# CommsTestBoard.net
KiCad netlist of a schematic drawn in EAGLE
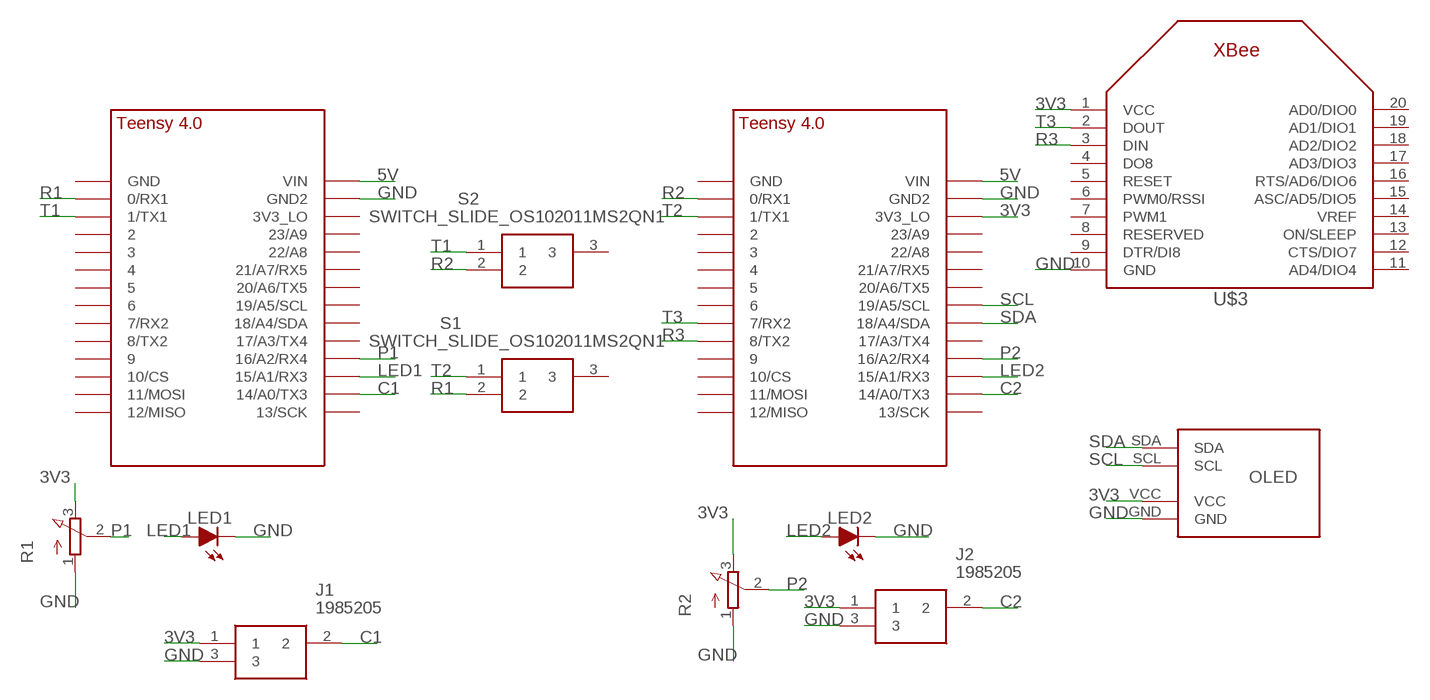
[diagram p0: schematic, sheet 1]

(export (version "E")
  (design (tool "Eeschema 10.0.6"))
  (components
    (comp (ref "J1")
      (value "1985205")
      (footprint "eagle-import:1985205")
      (fields (field (name "MOUSER_PART_NUMBER") "651-1985205"))
      (libsource (lib "eagle-import") (part "1985205"))
    )
    (comp (ref "J2")
      (value "1985205")
      (footprint "eagle-import:1985205")
      (fields (field (name "MOUSER_PART_NUMBER") "651-1985205"))
      (libsource (lib "eagle-import") (part "1985205"))
    )
    (comp (ref "LED1")
      (value "LED-5MM")
      (footprint "eagle-import:LED-5MM")
      (libsource (lib "eagle-import") (part "LED-5MM"))
    )
    (comp (ref "LED2")
      (value "LED-5MM")
      (footprint "eagle-import:LED-5MM")
      (libsource (lib "eagle-import") (part "LED-5MM"))
    )
    (comp (ref "R1")
      (value "POTENTIOMETER")
      (footprint "eagle-import:3RP_1610N")
      (libsource (lib "eagle-import") (part "POTENTIOMETER"))
    )
    (comp (ref "R2")
      (value "POTENTIOMETER")
      (footprint "eagle-import:3RP_1610N")
      (libsource (lib "eagle-import") (part "POTENTIOMETER"))
    )
    (comp (ref "S1")
      (value "SWITCH_SLIDE_OS102011MS2QN1")
      (footprint "eagle-import:OS102011MA1QN1")
      (fields
        (field (name "ARROW_PART_NUMBER") "OS102011MS2QN1")
        (field (name "MOUSER_PART_NUMBER") "611-OS102011MS2QN1")
      )
      (libsource (lib "eagle-import") (part "SWITCH_SLIDE_OS102011MS2QN1"))
    )
    (comp (ref "S2")
      (value "SWITCH_SLIDE_OS102011MS2QN1")
      (footprint "eagle-import:OS102011MA1QN1")
      (fields
        (field (name "ARROW_PART_NUMBER") "OS102011MS2QN1")
        (field (name "MOUSER_PART_NUMBER") "611-OS102011MS2QN1")
      )
      (libsource (lib "eagle-import") (part "SWITCH_SLIDE_OS102011MS2QN1"))
    )
    (comp (ref "U$1")
      (value "TEENSY_4.0_SIMPLE")
      (footprint "eagle-import:TEENSY_4.0_SIMPLE")
      (libsource (lib "eagle-import") (part "TEENSY_4.0_SIMPLE"))
    )
    (comp (ref "U$2")
      (value "TEENSY_4.0_SIMPLE")
      (footprint "eagle-import:TEENSY_4.0_SIMPLE")
      (libsource (lib "eagle-import") (part "TEENSY_4.0_SIMPLE"))
    )
    (comp (ref "U$3")
      (value "XBEE")
      (footprint "eagle-import:XBEE")
      (libsource (lib "eagle-import") (part "XBEE"))
    )
    (comp (ref "U$4")
      (value "OLED_SSD1306")
      (footprint "eagle-import:OLED_SSD1306")
      (libsource (lib "eagle-import") (part "OLED_SSD1306"))
    )
  )
  (nets
    (net (code "1") (name "/3V3") (class "Default")
      (node (ref "J1") (pin "1") (pinfunction "1_1") (pintype "bidirectional"))
      (node (ref "J2") (pin "1") (pinfunction "1_1") (pintype "bidirectional"))
      (node (ref "R1") (pin "3") (pinfunction "E_3") (pintype "passive"))
      (node (ref "R2") (pin "3") (pinfunction "E_3") (pintype "passive"))
      (node (ref "U$2") (pin "3V3_LO") (pinfunction "3V3_LO_3V3_LO") (pintype "bidirectional"))
      (node (ref "U$3") (pin "1") (pinfunction "VCC_1") (pintype "power_in"))
      (node (ref "U$4") (pin "VCC") (pinfunction "VCC_VCC") (pintype "bidirectional"))
    )
    (net (code "2") (name "/5V") (class "Default")
      (node (ref "U$1") (pin "VIN") (pinfunction "VIN_VIN") (pintype "bidirectional"))
      (node (ref "U$2") (pin "VIN") (pinfunction "VIN_VIN") (pintype "bidirectional"))
    )
    (net (code "3") (name "/C1") (class "Default")
      (node (ref "J1") (pin "2") (pinfunction "2_2") (pintype "bidirectional"))
      (node (ref "U$1") (pin "14/A0") (pinfunction "14/A0/TX3_14/A0") (pintype "bidirectional"))
    )
    (net (code "4") (name "/C2") (class "Default")
      (node (ref "J2") (pin "2") (pinfunction "2_2") (pintype "bidirectional"))
      (node (ref "U$2") (pin "14/A0") (pinfunction "14/A0/TX3_14/A0") (pintype "bidirectional"))
    )
    (net (code "5") (name "/GND") (class "Default")
      (node (ref "J1") (pin "3") (pinfunction "3_3") (pintype "bidirectional"))
      (node (ref "J2") (pin "3") (pinfunction "3_3") (pintype "bidirectional"))
      (node (ref "LED1") (pin "K") (pinfunction "C_K") (pintype "passive"))
      (node (ref "LED2") (pin "K") (pinfunction "C_K") (pintype "passive"))
      (node (ref "R1") (pin "1") (pinfunction "A_1") (pintype "passive"))
      (node (ref "R2") (pin "1") (pinfunction "A_1") (pintype "passive"))
      (node (ref "U$1") (pin "GND2") (pinfunction "GND2_GND2") (pintype "bidirectional"))
      (node (ref "U$2") (pin "GND2") (pinfunction "GND2_GND2") (pintype "bidirectional"))
      (node (ref "U$3") (pin "10") (pinfunction "GND_10") (pintype "power_in"))
      (node (ref "U$4") (pin "GND") (pinfunction "GND_GND") (pintype "bidirectional"))
    )
    (net (code "6") (name "/LED1") (class "Default")
      (node (ref "LED1") (pin "A") (pinfunction "A_A") (pintype "passive"))
      (node (ref "U$1") (pin "15/A1") (pinfunction "15/A1/RX3_15/A1") (pintype "bidirectional"))
    )
    (net (code "7") (name "/LED2") (class "Default")
      (node (ref "LED2") (pin "A") (pinfunction "A_A") (pintype "passive"))
      (node (ref "U$2") (pin "15/A1") (pinfunction "15/A1/RX3_15/A1") (pintype "bidirectional"))
    )
    (net (code "8") (name "/P1") (class "Default")
      (node (ref "R1") (pin "2") (pinfunction "S_2") (pintype "passive"))
      (node (ref "U$1") (pin "16/A2") (pinfunction "16/A2/RX4_16/A2") (pintype "bidirectional"))
    )
    (net (code "9") (name "/P2") (class "Default")
      (node (ref "R2") (pin "2") (pinfunction "S_2") (pintype "passive"))
      (node (ref "U$2") (pin "16/A2") (pinfunction "16/A2/RX4_16/A2") (pintype "bidirectional"))
    )
    (net (code "10") (name "/R1") (class "Default")
      (node (ref "S1") (pin "2") (pinfunction "2_2") (pintype "bidirectional"))
      (node (ref "U$1") (pin "0/RX") (pinfunction "0/RX1_0/RX") (pintype "bidirectional"))
    )
    (net (code "11") (name "/R2") (class "Default")
      (node (ref "S2") (pin "2") (pinfunction "2_2") (pintype "bidirectional"))
      (node (ref "U$2") (pin "0/RX") (pinfunction "0/RX1_0/RX") (pintype "bidirectional"))
    )
    (net (code "12") (name "/R3") (class "Default")
      (node (ref "U$2") (pin "8") (pinfunction "8/TX2_8") (pintype "bidirectional"))
      (node (ref "U$3") (pin "3") (pinfunction "DIN_3") (pintype "input"))
    )
    (net (code "13") (name "/SCL") (class "Default")
      (node (ref "U$2") (pin "19/A5/SCL") (pinfunction "19/A5/SCL_19/A5/SCL") (pintype "bidirectional"))
      (node (ref "U$4") (pin "SCL") (pinfunction "SCL_SCL") (pintype "bidirectional"))
    )
    (net (code "14") (name "/SDA") (class "Default")
      (node (ref "U$2") (pin "18/A4/SDA") (pinfunction "18/A4/SDA_18/A4/SDA") (pintype "bidirectional"))
      (node (ref "U$4") (pin "SDA") (pinfunction "SDA_SDA") (pintype "bidirectional"))
    )
    (net (code "15") (name "/T1") (class "Default")
      (node (ref "S2") (pin "1") (pinfunction "1_1") (pintype "bidirectional"))
      (node (ref "U$1") (pin "1/TX") (pinfunction "1/TX1_1/TX") (pintype "bidirectional"))
    )
    (net (code "16") (name "/T2") (class "Default")
      (node (ref "S1") (pin "1") (pinfunction "1_1") (pintype "bidirectional"))
      (node (ref "U$2") (pin "1/TX") (pinfunction "1/TX1_1/TX") (pintype "bidirectional"))
    )
    (net (code "17") (name "/T3") (class "Default")
      (node (ref "U$2") (pin "7") (pinfunction "7/RX2_7") (pintype "bidirectional"))
      (node (ref "U$3") (pin "2") (pinfunction "DOUT_2") (pintype "output"))
    )
    (net (code "18") (name "unconnected-(S1-Pad3)") (class "Default")
      (node (ref "S1") (pin "3") (pinfunction "3_3") (pintype "bidirectional"))
    )
    (net (code "19") (name "unconnected-(S2-Pad3)") (class "Default")
      (node (ref "S2") (pin "3") (pinfunction "3_3") (pintype "bidirectional"))
    )
    (net (code "20") (name "unconnected-(U$1-3-Pad3{slash}CANTX)") (class "Default")
      (node (ref "U$1") (pin "3/CANTX") (pinfunction "3_3/CANTX") (pintype "bidirectional"))
    )
    (net (code "21") (name "unconnected-(U$1-4-Pad4{slash}CANRX)") (class "Default")
      (node (ref "U$1") (pin "4/CANRX") (pinfunction "4_4/CANRX") (pintype "bidirectional"))
    )
    (net (code "22") (name "unconnected-(U$1-7{slash}RX2-Pad7)") (class "Default")
      (node (ref "U$1") (pin "7") (pinfunction "7/RX2_7") (pintype "bidirectional"))
    )
    (net (code "23") (name "unconnected-(U$1-8{slash}TX2-Pad8)") (class "Default")
      (node (ref "U$1") (pin "8") (pinfunction "8/TX2_8") (pintype "bidirectional"))
    )
    (net (code "24") (name "unconnected-(U$1-9-Pad9{slash}CS)") (class "Default")
      (node (ref "U$1") (pin "9/CS") (pinfunction "9_9/CS") (pintype "bidirectional"))
    )
    (net (code "25") (name "unconnected-(U$1-17{slash}A3{slash}TX4-Pad17{slash}A3)") (class "Default")
      (node (ref "U$1") (pin "17/A3") (pinfunction "17/A3/TX4_17/A3") (pintype "bidirectional"))
    )
    (net (code "26") (name "unconnected-(U$1-20{slash}A6{slash}TX5-Pad20{slash}A6)") (class "Default")
      (node (ref "U$1") (pin "20/A6") (pinfunction "20/A6/TX5_20/A6") (pintype "bidirectional"))
    )
    (net (code "27") (name "unconnected-(U$1-21{slash}A7{slash}RX5-Pad21{slash}A7)") (class "Default")
      (node (ref "U$1") (pin "21/A7") (pinfunction "21/A7/RX5_21/A7") (pintype "bidirectional"))
    )
    (net (code "28") (name "unconnected-(U$1-Pad2)") (class "Default")
      (node (ref "U$1") (pin "2") (pinfunction "2_2") (pintype "bidirectional"))
    )
    (net (code "29") (name "unconnected-(U$1-Pad3V3_LO)") (class "Default")
      (node (ref "U$1") (pin "3V3_LO") (pinfunction "3V3_LO_3V3_LO") (pintype "bidirectional"))
    )
    (net (code "30") (name "unconnected-(U$1-Pad5)") (class "Default")
      (node (ref "U$1") (pin "5") (pinfunction "5_5") (pintype "bidirectional"))
    )
    (net (code "31") (name "unconnected-(U$1-Pad6)") (class "Default")
      (node (ref "U$1") (pin "6") (pinfunction "6_6") (pintype "bidirectional"))
    )
    (net (code "32") (name "unconnected-(U$1-Pad10{slash}CS)") (class "Default")
      (node (ref "U$1") (pin "10/CS") (pinfunction "10/CS_10/CS") (pintype "bidirectional"))
    )
    (net (code "33") (name "unconnected-(U$1-Pad11{slash}MOSI)") (class "Default")
      (node (ref "U$1") (pin "11/MOSI") (pinfunction "11/MOSI_11/MOSI") (pintype "bidirectional"))
    )
    (net (code "34") (name "unconnected-(U$1-Pad12{slash}MISO)") (class "Default")
      (node (ref "U$1") (pin "12/MISO") (pinfunction "12/MISO_12/MISO") (pintype "bidirectional"))
    )
    (net (code "35") (name "unconnected-(U$1-Pad13{slash}SCK)") (class "Default")
      (node (ref "U$1") (pin "13/SCK") (pinfunction "13/SCK_13/SCK") (pintype "bidirectional"))
    )
    (net (code "36") (name "unconnected-(U$1-Pad18{slash}A4{slash}SDA)") (class "Default")
      (node (ref "U$1") (pin "18/A4/SDA") (pinfunction "18/A4/SDA_18/A4/SDA") (pintype "bidirectional"))
    )
    (net (code "37") (name "unconnected-(U$1-Pad19{slash}A5{slash}SCL)") (class "Default")
      (node (ref "U$1") (pin "19/A5/SCL") (pinfunction "19/A5/SCL_19/A5/SCL") (pintype "bidirectional"))
    )
    (net (code "38") (name "unconnected-(U$1-Pad22{slash}A8)") (class "Default")
      (node (ref "U$1") (pin "22/A8") (pinfunction "22/A8_22/A8") (pintype "bidirectional"))
    )
    (net (code "39") (name "unconnected-(U$1-Pad23{slash}A9)") (class "Default")
      (node (ref "U$1") (pin "23/A9") (pinfunction "23/A9_23/A9") (pintype "bidirectional"))
    )
    (net (code "40") (name "unconnected-(U$1-PadGND)") (class "Default")
      (node (ref "U$1") (pin "GND") (pinfunction "GND_GND") (pintype "bidirectional"))
    )
    (net (code "41") (name "unconnected-(U$2-3-Pad3{slash}CANTX)") (class "Default")
      (node (ref "U$2") (pin "3/CANTX") (pinfunction "3_3/CANTX") (pintype "bidirectional"))
    )
    (net (code "42") (name "unconnected-(U$2-4-Pad4{slash}CANRX)") (class "Default")
      (node (ref "U$2") (pin "4/CANRX") (pinfunction "4_4/CANRX") (pintype "bidirectional"))
    )
    (net (code "43") (name "unconnected-(U$2-9-Pad9{slash}CS)") (class "Default")
      (node (ref "U$2") (pin "9/CS") (pinfunction "9_9/CS") (pintype "bidirectional"))
    )
    (net (code "44") (name "unconnected-(U$2-17{slash}A3{slash}TX4-Pad17{slash}A3)") (class "Default")
      (node (ref "U$2") (pin "17/A3") (pinfunction "17/A3/TX4_17/A3") (pintype "bidirectional"))
    )
    (net (code "45") (name "unconnected-(U$2-20{slash}A6{slash}TX5-Pad20{slash}A6)") (class "Default")
      (node (ref "U$2") (pin "20/A6") (pinfunction "20/A6/TX5_20/A6") (pintype "bidirectional"))
    )
    (net (code "46") (name "unconnected-(U$2-21{slash}A7{slash}RX5-Pad21{slash}A7)") (class "Default")
      (node (ref "U$2") (pin "21/A7") (pinfunction "21/A7/RX5_21/A7") (pintype "bidirectional"))
    )
    (net (code "47") (name "unconnected-(U$2-Pad2)") (class "Default")
      (node (ref "U$2") (pin "2") (pinfunction "2_2") (pintype "bidirectional"))
    )
    (net (code "48") (name "unconnected-(U$2-Pad5)") (class "Default")
      (node (ref "U$2") (pin "5") (pinfunction "5_5") (pintype "bidirectional"))
    )
    (net (code "49") (name "unconnected-(U$2-Pad6)") (class "Default")
      (node (ref "U$2") (pin "6") (pinfunction "6_6") (pintype "bidirectional"))
    )
    (net (code "50") (name "unconnected-(U$2-Pad10{slash}CS)") (class "Default")
      (node (ref "U$2") (pin "10/CS") (pinfunction "10/CS_10/CS") (pintype "bidirectional"))
    )
    (net (code "51") (name "unconnected-(U$2-Pad11{slash}MOSI)") (class "Default")
      (node (ref "U$2") (pin "11/MOSI") (pinfunction "11/MOSI_11/MOSI") (pintype "bidirectional"))
    )
    (net (code "52") (name "unconnected-(U$2-Pad12{slash}MISO)") (class "Default")
      (node (ref "U$2") (pin "12/MISO") (pinfunction "12/MISO_12/MISO") (pintype "bidirectional"))
    )
    (net (code "53") (name "unconnected-(U$2-Pad13{slash}SCK)") (class "Default")
      (node (ref "U$2") (pin "13/SCK") (pinfunction "13/SCK_13/SCK") (pintype "bidirectional"))
    )
    (net (code "54") (name "unconnected-(U$2-Pad22{slash}A8)") (class "Default")
      (node (ref "U$2") (pin "22/A8") (pinfunction "22/A8_22/A8") (pintype "bidirectional"))
    )
    (net (code "55") (name "unconnected-(U$2-Pad23{slash}A9)") (class "Default")
      (node (ref "U$2") (pin "23/A9") (pinfunction "23/A9_23/A9") (pintype "bidirectional"))
    )
    (net (code "56") (name "unconnected-(U$2-PadGND)") (class "Default")
      (node (ref "U$2") (pin "GND") (pinfunction "GND_GND") (pintype "bidirectional"))
    )
    (net (code "57") (name "unconnected-(U$3-AD0{slash}DIO0-Pad20)") (class "Default")
      (node (ref "U$3") (pin "20") (pinfunction "AD0/DIO0_20") (pintype "bidirectional"))
    )
    (net (code "58") (name "unconnected-(U$3-AD1{slash}DIO1-Pad19)") (class "Default")
      (node (ref "U$3") (pin "19") (pinfunction "AD1/DIO1_19") (pintype "bidirectional"))
    )
    (net (code "59") (name "unconnected-(U$3-AD2{slash}DIO2-Pad18)") (class "Default")
      (node (ref "U$3") (pin "18") (pinfunction "AD2/DIO2_18") (pintype "bidirectional"))
    )
    (net (code "60") (name "unconnected-(U$3-AD3{slash}DIO3-Pad17)") (class "Default")
      (node (ref "U$3") (pin "17") (pinfunction "AD3/DIO3_17") (pintype "bidirectional"))
    )
    (net (code "61") (name "unconnected-(U$3-AD4{slash}DIO4-Pad11)") (class "Default")
      (node (ref "U$3") (pin "11") (pinfunction "AD4/DIO4_11") (pintype "bidirectional"))
    )
    (net (code "62") (name "unconnected-(U$3-ASC{slash}AD5{slash}DIO5-Pad15)") (class "Default")
      (node (ref "U$3") (pin "15") (pinfunction "ASC/AD5/DIO5_15") (pintype "bidirectional"))
    )
    (net (code "63") (name "unconnected-(U$3-CTS{slash}DIO7-Pad12)") (class "Default")
      (node (ref "U$3") (pin "12") (pinfunction "CTS/DIO7_12") (pintype "bidirectional"))
    )
    (net (code "64") (name "unconnected-(U$3-DO8-Pad4)") (class "Default")
      (node (ref "U$3") (pin "4") (pinfunction "DO8_4") (pintype "output"))
    )
    (net (code "65") (name "unconnected-(U$3-DTR{slash}DI8-Pad9)") (class "Default")
      (node (ref "U$3") (pin "9") (pinfunction "DTR/DI8_9") (pintype "input"))
    )
    (net (code "66") (name "unconnected-(U$3-ON{slash}SLEEP-Pad13)") (class "Default")
      (node (ref "U$3") (pin "13") (pinfunction "ON/SLEEP_13") (pintype "output"))
    )
    (net (code "67") (name "unconnected-(U$3-PWM0{slash}RSSI-Pad6)") (class "Default")
      (node (ref "U$3") (pin "6") (pinfunction "PWM0/RSSI_6") (pintype "output"))
    )
    (net (code "68") (name "unconnected-(U$3-PWM1-Pad7)") (class "Default")
      (node (ref "U$3") (pin "7") (pinfunction "PWM1_7") (pintype "output"))
    )
    (net (code "69") (name "unconnected-(U$3-RESERVED-Pad8)") (class "Default")
      (node (ref "U$3") (pin "8") (pinfunction "RESERVED_8") (pintype "no_connect"))
    )
    (net (code "70") (name "unconnected-(U$3-RESET-Pad5)") (class "Default")
      (node (ref "U$3") (pin "5") (pinfunction "RESET_5") (pintype "input"))
    )
    (net (code "71") (name "unconnected-(U$3-RTS{slash}AD6{slash}DIO6-Pad16)") (class "Default")
      (node (ref "U$3") (pin "16") (pinfunction "RTS/AD6/DIO6_16") (pintype "bidirectional"))
    )
    (net (code "72") (name "unconnected-(U$3-VREF-Pad14)") (class "Default")
      (node (ref "U$3") (pin "14") (pinfunction "VREF_14") (pintype "input"))
    )
  )
)
